# SchematCzujnikUV.net
KiCad netlist of a schematic drawn in Altium Designer
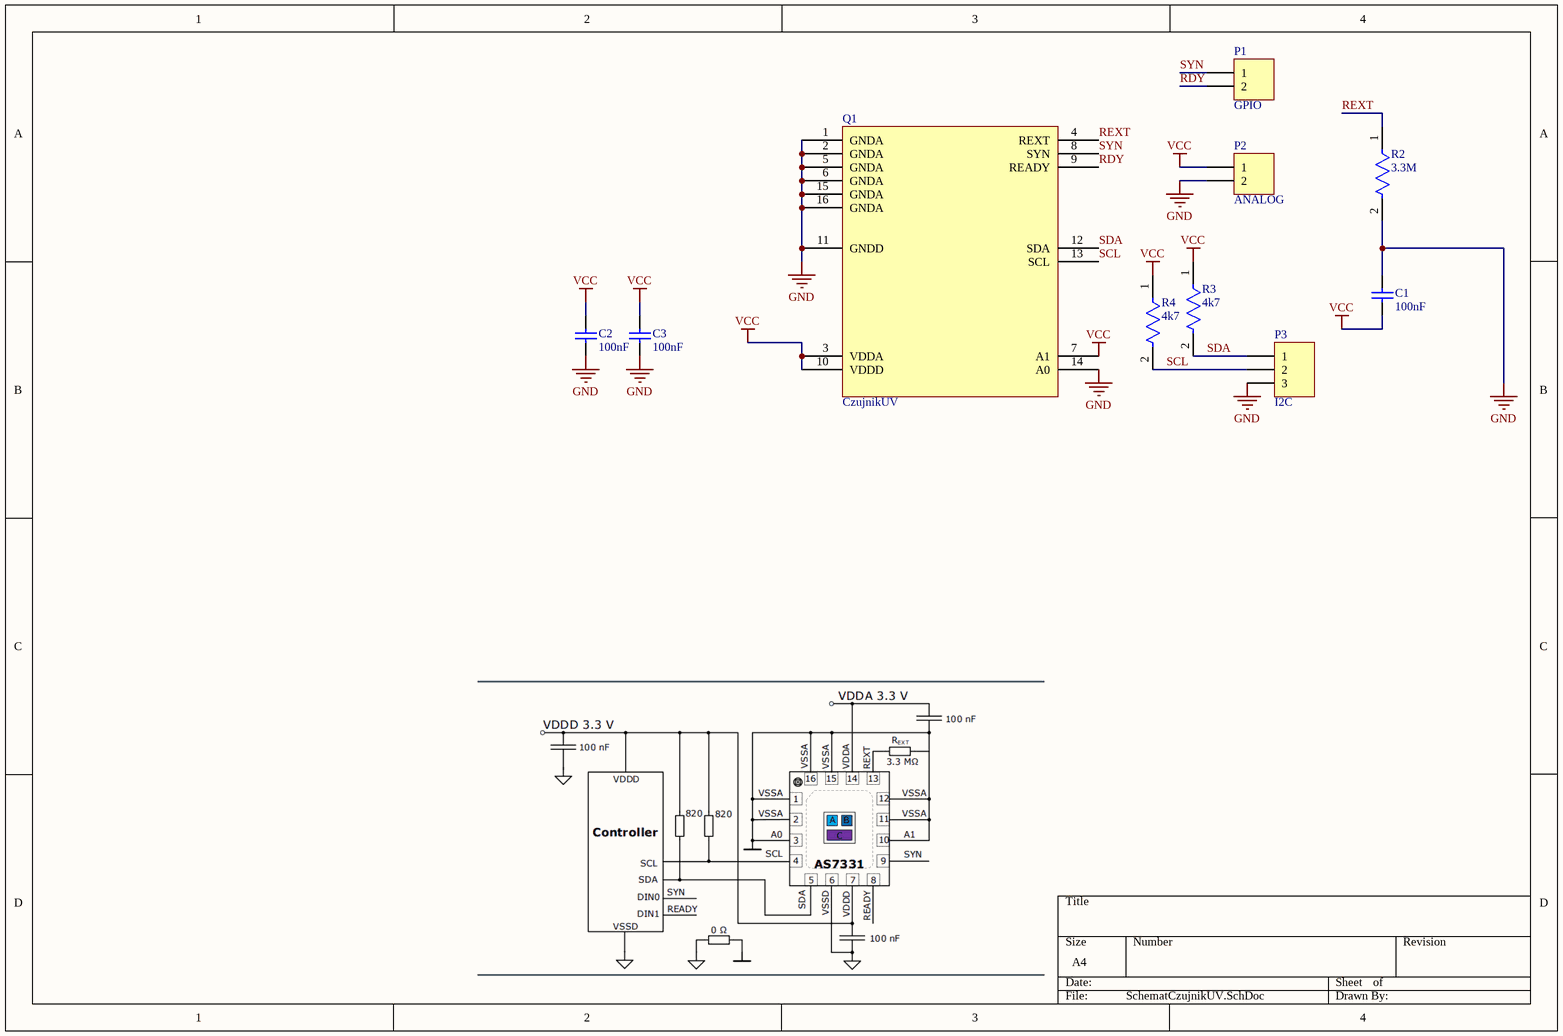
[diagram p0: SchematCzujnikUV.SchDoc]

(export (version "E")
  (design (tool "Eeschema 10.0.6"))
  (components
    (comp (ref "C1")
      (value "100nF")
      (footprint "1608[0603]")
      (description "Capacitor (Semiconductor SIM Model)")
      (fields (field (name "PUBLISHER") "Altium Limited"))
      (libsource (lib "Miscellaneous Devices") (part "Cap Semi"))
    )
    (comp (ref "C2")
      (value "100nF")
      (footprint "1608[0603]")
      (description "Capacitor (Semiconductor SIM Model)")
      (fields (field (name "PUBLISHER") "Altium Limited"))
      (libsource (lib "Miscellaneous Devices") (part "Cap Semi"))
    )
    (comp (ref "C3")
      (value "100nF")
      (footprint "1608[0603]")
      (description "Capacitor (Semiconductor SIM Model)")
      (fields (field (name "PUBLISHER") "Altium Limited"))
      (libsource (lib "Miscellaneous Devices") (part "Cap Semi"))
    )
    (comp (ref "P1")
      (value "GPIO")
      (footprint "HDR1X2")
      (description "Header, 2-Pin")
      (fields (field (name "PUBLISHER") "Altium Limited"))
      (libsource (lib "Miscellaneous Connectors") (part "Header 2"))
    )
    (comp (ref "P2")
      (value "ANALOG")
      (footprint "HDR1X2")
      (description "Header, 2-Pin")
      (fields (field (name "PUBLISHER") "Altium Limited"))
      (libsource (lib "Miscellaneous Connectors") (part "Header 2"))
    )
    (comp (ref "P3")
      (value "I2C")
      (footprint "HDR1X3")
      (description "Header, 3-Pin")
      (fields (field (name "PUBLISHER") "Altium Limited"))
      (libsource (lib "Miscellaneous Connectors") (part "Header 3"))
    )
    (comp (ref "Q1")
      (value "CzujnikUV")
      (footprint "MateuszPytka:AS7331")
      (libsource (lib "Płytka") (part "CzujnikUV"))
    )
    (comp (ref "R2")
      (value "3.3M")
      (footprint "FP-CRCW0603-e3-MFG")
      (description "RES Thick Film, 10kΩ, 1%, 0.1W, 100ppm/°C, 0603")
      (fields (field (name "TOLERANCE") "1%"))
      (libsource (lib "Altium Content Vault") (part "1029c3af85768c4190bb7ad29bc67b5"))
    )
    (comp (ref "R3")
      (value "4k7")
      (footprint "FP-CRCW0603-e3-MFG")
      (description "RES Thick Film, 10kΩ, 1%, 0.1W, 100ppm/°C, 0603")
      (fields (field (name "TOLERANCE") "1%"))
      (libsource (lib "Altium Content Vault") (part "1029c3af85768c4190bb7ad29bc67b5"))
    )
    (comp (ref "R4")
      (value "4k7")
      (footprint "FP-CRCW0603-e3-MFG")
      (description "RES Thick Film, 10kΩ, 1%, 0.1W, 100ppm/°C, 0603")
      (fields (field (name "TOLERANCE") "1%"))
      (libsource (lib "Altium Content Vault") (part "1029c3af85768c4190bb7ad29bc67b5"))
    )
  )
  (nets
    (net (code "1") (name "/RDY") (class "Default")
      (node (ref "P1") (pin "2") (pinfunction "2_2") (pintype "passive"))
      (node (ref "Q1") (pin "9") (pinfunction "READY_9") (pintype "passive"))
    )
    (net (code "2") (name "/REXT") (class "Default")
      (node (ref "Q1") (pin "4") (pinfunction "REXT_4") (pintype "passive"))
      (node (ref "R2") (pin "1") (pinfunction "1_1") (pintype "passive"))
    )
    (net (code "3") (name "/SCL") (class "Default")
      (node (ref "P3") (pin "2") (pinfunction "2_2") (pintype "passive"))
      (node (ref "Q1") (pin "13") (pinfunction "SCL_13") (pintype "passive"))
      (node (ref "R4") (pin "2") (pinfunction "2_2") (pintype "passive"))
    )
    (net (code "4") (name "/SDA") (class "Default")
      (node (ref "P3") (pin "1") (pinfunction "1_1") (pintype "passive"))
      (node (ref "Q1") (pin "12") (pinfunction "SDA_12") (pintype "passive"))
      (node (ref "R3") (pin "2") (pinfunction "2_2") (pintype "passive"))
    )
    (net (code "5") (name "/SYN") (class "Default")
      (node (ref "P1") (pin "1") (pinfunction "1_1") (pintype "passive"))
      (node (ref "Q1") (pin "8") (pinfunction "SYN_8") (pintype "passive"))
    )
    (net (code "6") (name "GND") (class "Default")
      (node (ref "C1") (pin "1") (pinfunction "1_1") (pintype "passive"))
      (node (ref "C2") (pin "2") (pinfunction "2_2") (pintype "passive"))
      (node (ref "C3") (pin "2") (pinfunction "2_2") (pintype "passive"))
      (node (ref "P2") (pin "2") (pinfunction "2_2") (pintype "passive"))
      (node (ref "P3") (pin "3") (pinfunction "3_3") (pintype "passive"))
      (node (ref "Q1") (pin "1") (pinfunction "GNDA_1") (pintype "passive"))
      (node (ref "Q1") (pin "11") (pinfunction "GNDD_11") (pintype "passive"))
      (node (ref "Q1") (pin "14") (pinfunction "A0_14") (pintype "passive"))
      (node (ref "Q1") (pin "15") (pinfunction "GNDA_15") (pintype "passive"))
      (node (ref "Q1") (pin "16") (pinfunction "GNDA_16") (pintype "passive"))
      (node (ref "Q1") (pin "2") (pinfunction "GNDA_2") (pintype "passive"))
      (node (ref "Q1") (pin "5") (pinfunction "GNDA_5") (pintype "passive"))
      (node (ref "Q1") (pin "6") (pinfunction "GNDA_6") (pintype "passive"))
      (node (ref "R2") (pin "2") (pinfunction "2_2") (pintype "passive"))
    )
    (net (code "7") (name "VCC") (class "Default")
      (node (ref "C1") (pin "2") (pinfunction "2_2") (pintype "passive"))
      (node (ref "C2") (pin "1") (pinfunction "1_1") (pintype "passive"))
      (node (ref "C3") (pin "1") (pinfunction "1_1") (pintype "passive"))
      (node (ref "P2") (pin "1") (pinfunction "1_1") (pintype "passive"))
      (node (ref "Q1") (pin "10") (pinfunction "VDDD_10") (pintype "passive"))
      (node (ref "Q1") (pin "3") (pinfunction "VDDA_3") (pintype "passive"))
      (node (ref "Q1") (pin "7") (pinfunction "A1_7") (pintype "passive"))
      (node (ref "R3") (pin "1") (pinfunction "1_1") (pintype "passive"))
      (node (ref "R4") (pin "1") (pinfunction "1_1") (pintype "passive"))
    )
  )
)
